# LCDCommonBoard.net
KiCad netlist of a schematic drawn in Altium Designer
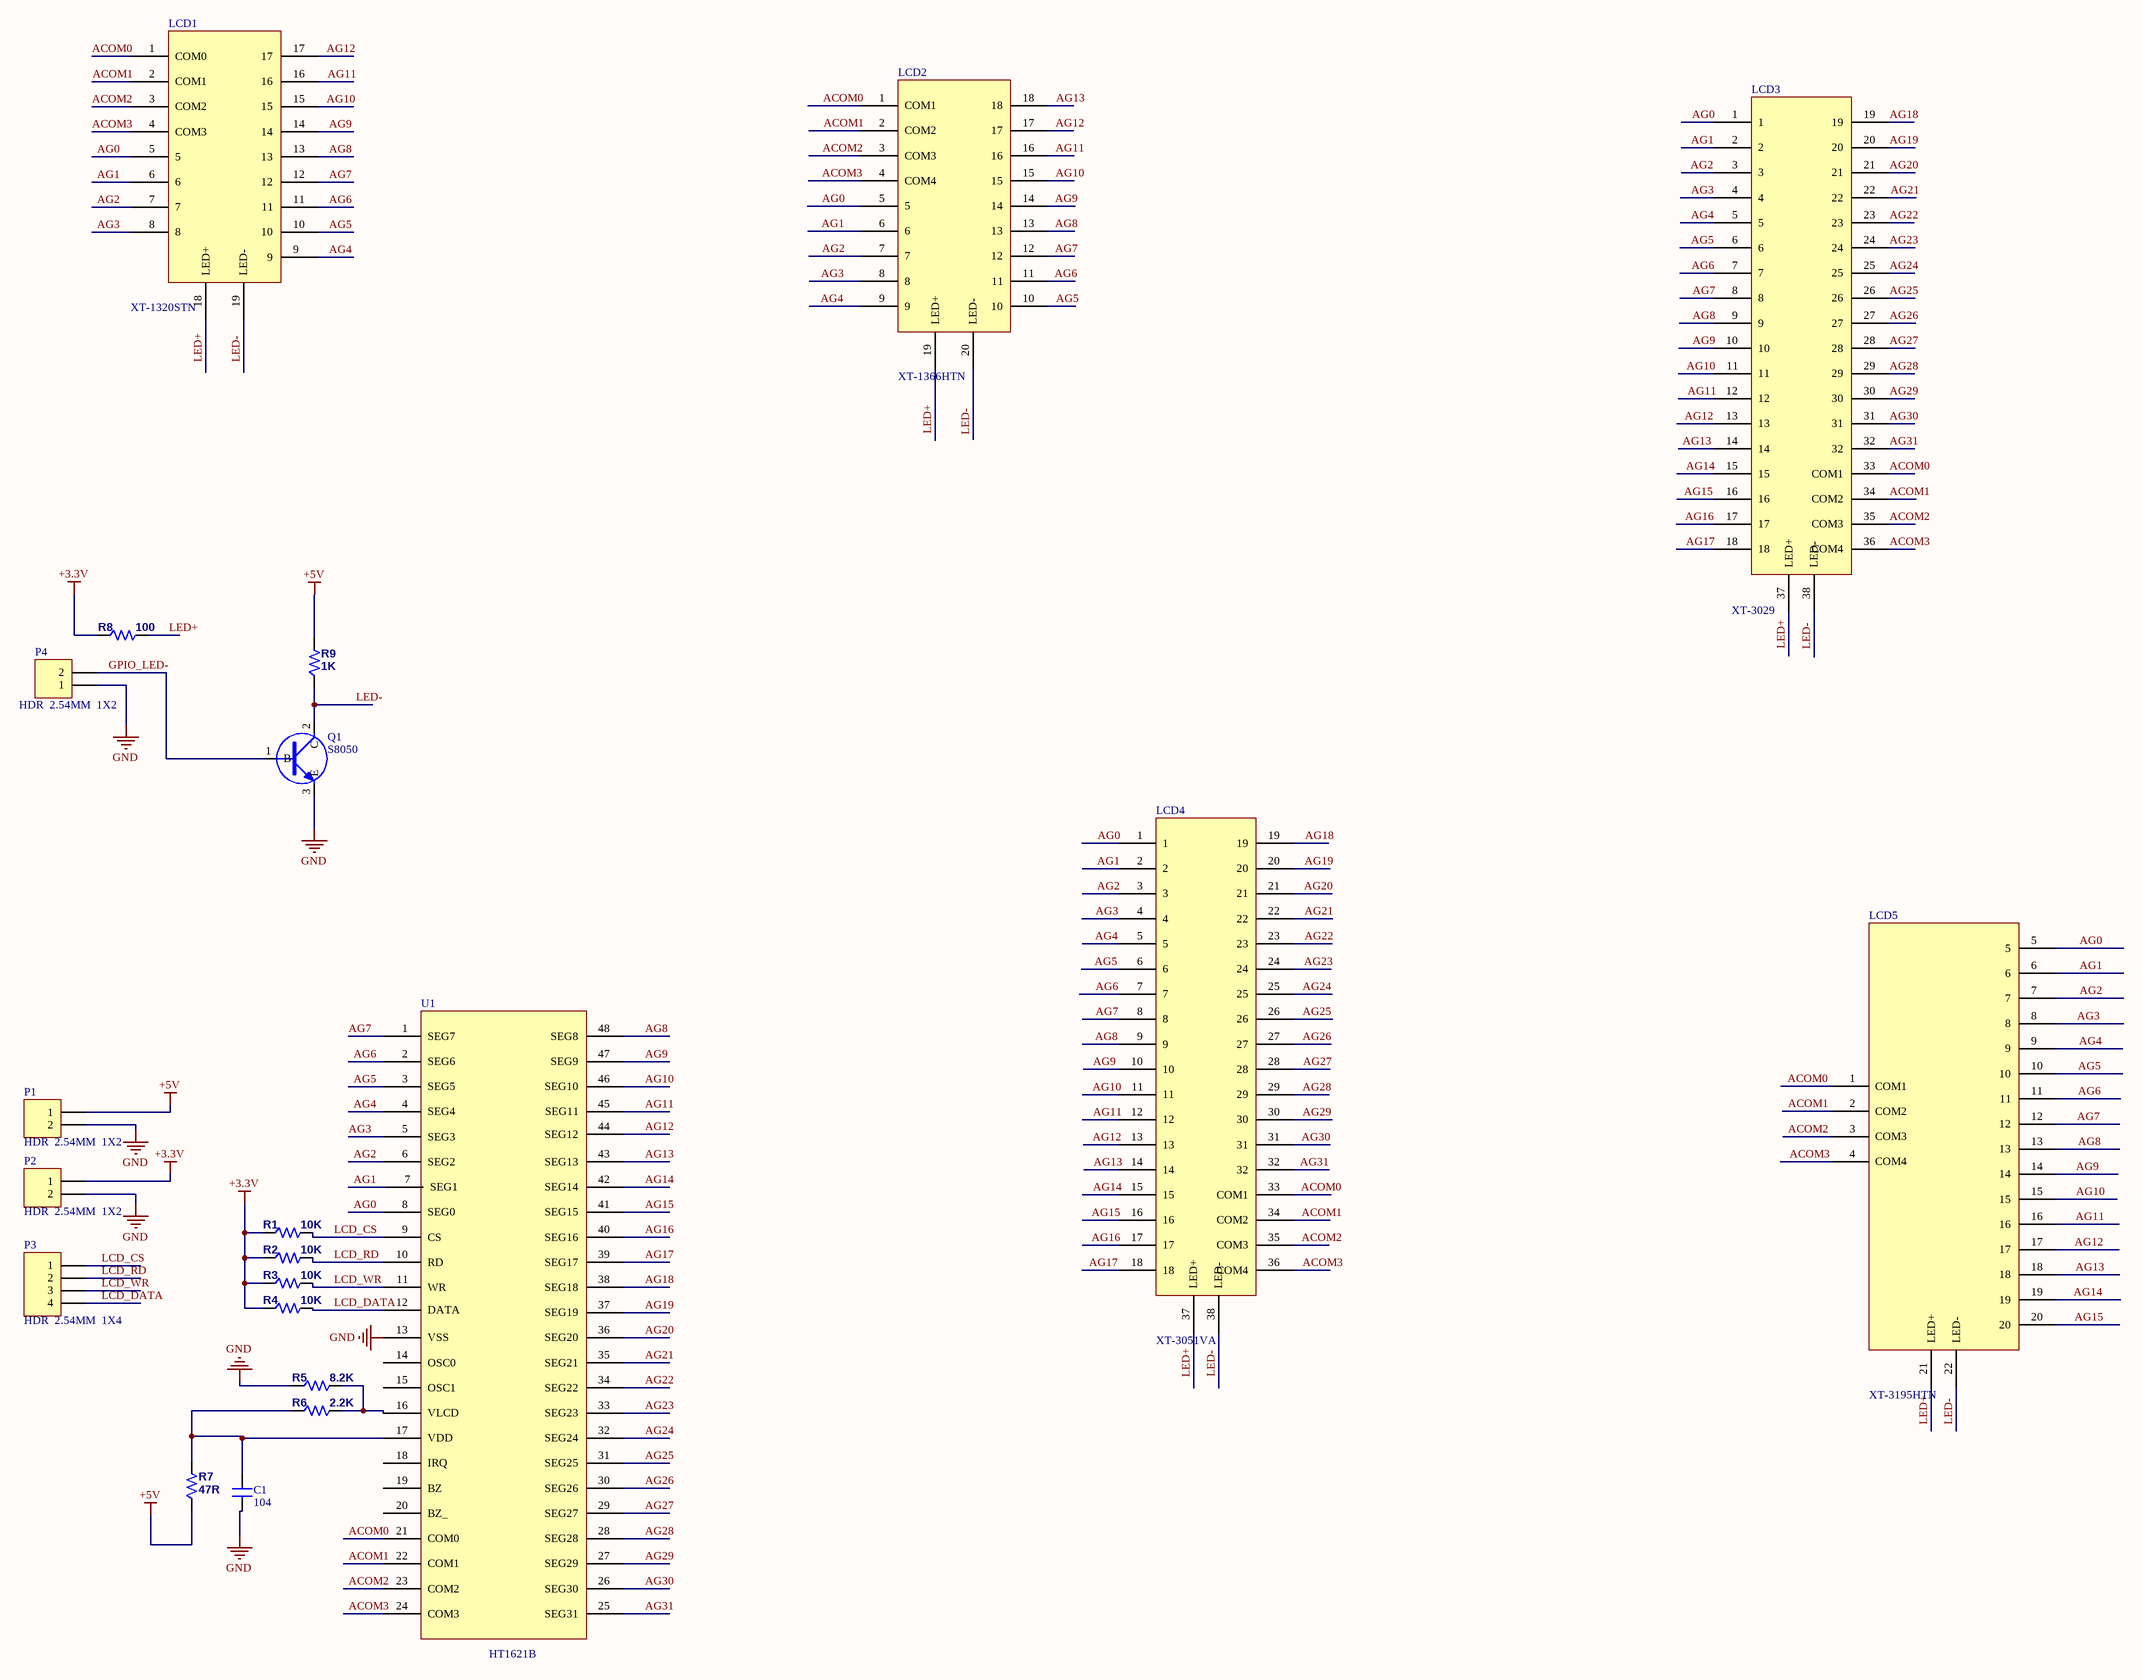
[diagram p0: LCDCommonBoard.SchDoc]

(export (version "E")
  (design (tool "Eeschema 10.0.6"))
  (components
    (comp (ref "C1")
      (value "104")
      (footprint "C0603")
      (description "查不到")
      (libsource (lib "兰格封装") (part "CAP1_60"))
    )
    (comp (ref "LCD1")
      (value "XT-1320STN")
      (footprint "LCD_8+9PIN_21X22")
      (libsource (lib "LCD") (part "XT-1320STN"))
    )
    (comp (ref "LCD2")
      (value "XT-1366HTN")
      (footprint "LCD_18PIN_20X16")
      (libsource (lib "LCD") (part "XT-1366HTN"))
    )
    (comp (ref "LCD3")
      (value "XT-3029")
      (footprint "LCD_36PIN_93X33")
      (libsource (lib "LCD") (part "XT-3029"))
    )
    (comp (ref "LCD4")
      (value "XT-3051VA")
      (footprint "LCD_36PIN_68x26.4")
      (libsource (lib "LCD") (part "XT-3051VA"))
    )
    (comp (ref "LCD5")
      (value "XT-3195HTN")
      (footprint "LCD_4+16PIN_15.5x22")
      (libsource (lib "LCD") (part "XT-3195HTN"))
    )
    (comp (ref "P1")
      (value "HDR  2.54MM  1X2")
      (footprint "HDR-1x2")
      (libsource (lib "排针排座") (part "HDR  2.54MM  1X2"))
    )
    (comp (ref "P2")
      (value "HDR  2.54MM  1X2")
      (footprint "HDR-1x2")
      (libsource (lib "排针排座") (part "HDR  2.54MM  1X2"))
    )
    (comp (ref "P3")
      (value "HDR  2.54MM  1X4")
      (footprint "HDR-1X4")
      (libsource (lib "排针排座") (part "HDR  2.54MM  1X4"))
    )
    (comp (ref "P4")
      (value "HDR  2.54MM  1X2")
      (footprint "HDR-1x2")
      (libsource (lib "") (part "HDR  2.54MM  1X2_1"))
    )
    (comp (ref "Q1") (value "S8050") (footprint "SOT 23") (libsource (lib "兰格封装") (part "NPN  东芝管2SA5200")))
    (comp (ref "R1")
      (value "10K")
      (footprint "R0603")
      (description "1206  K  5%  HS  贴片电阻")
      (libsource (lib "兰格封装") (part "RES1"))
    )
    (comp (ref "R2")
      (value "10K")
      (footprint "R0603")
      (description "1206  K  5%  HS  贴片电阻")
      (libsource (lib "兰格封装") (part "RES1"))
    )
    (comp (ref "R3")
      (value "10K")
      (footprint "R0603")
      (description "1206  K  5%  HS  贴片电阻")
      (libsource (lib "兰格封装") (part "RES1"))
    )
    (comp (ref "R4")
      (value "10K")
      (footprint "R0603")
      (description "1206  K  5%  HS  贴片电阻")
      (libsource (lib "兰格封装") (part "RES1"))
    )
    (comp (ref "R5")
      (value "8.2K")
      (footprint "R0603")
      (description "1206  K  5%  HS  贴片电阻")
      (libsource (lib "兰格封装") (part "RES1"))
    )
    (comp (ref "R6")
      (value "2.2K")
      (footprint "R0603")
      (description "1206  K  5%  HS  贴片电阻")
      (libsource (lib "兰格封装") (part "RES1"))
    )
    (comp (ref "R7")
      (value "47R")
      (footprint "R0603")
      (description "1206  K  5%  HS  贴片电阻")
      (libsource (lib "兰格封装") (part "RES1"))
    )
    (comp (ref "R8")
      (value "100")
      (footprint "R0805")
      (description "1206  K  5%  HS  贴片电阻")
      (libsource (lib "兰格封装") (part "RES1"))
    )
    (comp (ref "R9")
      (value "1K")
      (footprint "R0603")
      (description "1206  K  5%  HS  贴片电阻")
      (libsource (lib "兰格封装") (part "RES1"))
    )
    (comp (ref "U1") (value "HT1621B") (footprint "SSOP-48") (libsource (lib "集成IC") (part "HT1621B")))
  )
  (nets
    (net (code "1") (name "+3.3V") (class "Default")
      (node (ref "P2") (pin "1") (pinfunction "1_1") (pintype "passive"))
      (node (ref "R1") (pin "1") (pintype "passive"))
      (node (ref "R2") (pin "1") (pintype "passive"))
      (node (ref "R3") (pin "1") (pintype "passive"))
      (node (ref "R4") (pin "1") (pintype "passive"))
      (node (ref "R8") (pin "1") (pintype "passive"))
    )
    (net (code "2") (name "+5V") (class "Default")
      (node (ref "P1") (pin "1") (pinfunction "1_1") (pintype "passive"))
      (node (ref "R7") (pin "1") (pintype "passive"))
      (node (ref "R9") (pin "2") (pintype "passive"))
    )
    (net (code "3") (name "/ACOM0") (class "Default")
      (node (ref "LCD1") (pin "1") (pinfunction "COM0_1") (pintype "passive"))
      (node (ref "LCD2") (pin "1") (pinfunction "COM1_1") (pintype "passive"))
      (node (ref "LCD3") (pin "33") (pinfunction "COM1_33") (pintype "passive"))
      (node (ref "LCD4") (pin "33") (pinfunction "COM1_33") (pintype "passive"))
      (node (ref "LCD5") (pin "1") (pinfunction "COM1_1") (pintype "passive"))
      (node (ref "U1") (pin "21") (pinfunction "COM0_21") (pintype "passive"))
    )
    (net (code "4") (name "/ACOM1") (class "Default")
      (node (ref "LCD1") (pin "2") (pinfunction "COM1_2") (pintype "passive"))
      (node (ref "LCD2") (pin "2") (pinfunction "COM2_2") (pintype "passive"))
      (node (ref "LCD3") (pin "34") (pinfunction "COM2_34") (pintype "passive"))
      (node (ref "LCD4") (pin "34") (pinfunction "COM2_34") (pintype "passive"))
      (node (ref "LCD5") (pin "2") (pinfunction "COM2_2") (pintype "passive"))
      (node (ref "U1") (pin "22") (pinfunction "COM1_22") (pintype "passive"))
    )
    (net (code "5") (name "/ACOM2") (class "Default")
      (node (ref "LCD1") (pin "3") (pinfunction "COM2_3") (pintype "passive"))
      (node (ref "LCD2") (pin "3") (pinfunction "COM3_3") (pintype "passive"))
      (node (ref "LCD3") (pin "35") (pinfunction "COM3_35") (pintype "passive"))
      (node (ref "LCD4") (pin "35") (pinfunction "COM3_35") (pintype "passive"))
      (node (ref "LCD5") (pin "3") (pinfunction "COM3_3") (pintype "passive"))
      (node (ref "U1") (pin "23") (pinfunction "COM2_23") (pintype "passive"))
    )
    (net (code "6") (name "/ACOM3") (class "Default")
      (node (ref "LCD1") (pin "4") (pinfunction "COM3_4") (pintype "passive"))
      (node (ref "LCD2") (pin "4") (pinfunction "COM4_4") (pintype "passive"))
      (node (ref "LCD3") (pin "36") (pinfunction "COM4_36") (pintype "passive"))
      (node (ref "LCD4") (pin "36") (pinfunction "COM4_36") (pintype "passive"))
      (node (ref "LCD5") (pin "4") (pinfunction "COM4_4") (pintype "passive"))
      (node (ref "U1") (pin "24") (pinfunction "COM3_24") (pintype "passive"))
    )
    (net (code "7") (name "/AG0") (class "Default")
      (node (ref "LCD1") (pin "5") (pinfunction "5_5") (pintype "passive"))
      (node (ref "LCD2") (pin "5") (pinfunction "5_5") (pintype "passive"))
      (node (ref "LCD3") (pin "1") (pinfunction "1_1") (pintype "passive"))
      (node (ref "LCD4") (pin "1") (pinfunction "1_1") (pintype "passive"))
      (node (ref "LCD5") (pin "5") (pinfunction "5_5") (pintype "passive"))
      (node (ref "U1") (pin "8") (pinfunction "SEG0_8") (pintype "passive"))
    )
    (net (code "8") (name "/AG1") (class "Default")
      (node (ref "LCD1") (pin "6") (pinfunction "6_6") (pintype "passive"))
      (node (ref "LCD2") (pin "6") (pinfunction "6_6") (pintype "passive"))
      (node (ref "LCD3") (pin "2") (pinfunction "2_2") (pintype "passive"))
      (node (ref "LCD4") (pin "2") (pinfunction "2_2") (pintype "passive"))
      (node (ref "LCD5") (pin "6") (pinfunction "6_6") (pintype "passive"))
      (node (ref "U1") (pin "7") (pinfunction "SEG1_7") (pintype "passive"))
    )
    (net (code "9") (name "/AG2") (class "Default")
      (node (ref "LCD1") (pin "7") (pinfunction "7_7") (pintype "passive"))
      (node (ref "LCD2") (pin "7") (pinfunction "7_7") (pintype "passive"))
      (node (ref "LCD3") (pin "3") (pinfunction "3_3") (pintype "passive"))
      (node (ref "LCD4") (pin "3") (pinfunction "3_3") (pintype "passive"))
      (node (ref "LCD5") (pin "7") (pinfunction "7_7") (pintype "passive"))
      (node (ref "U1") (pin "6") (pinfunction "SEG2_6") (pintype "passive"))
    )
    (net (code "10") (name "/AG3") (class "Default")
      (node (ref "LCD1") (pin "8") (pinfunction "8_8") (pintype "passive"))
      (node (ref "LCD2") (pin "8") (pinfunction "8_8") (pintype "passive"))
      (node (ref "LCD3") (pin "4") (pinfunction "4_4") (pintype "passive"))
      (node (ref "LCD4") (pin "4") (pinfunction "4_4") (pintype "passive"))
      (node (ref "LCD5") (pin "8") (pinfunction "8_8") (pintype "passive"))
      (node (ref "U1") (pin "5") (pinfunction "SEG3_5") (pintype "passive"))
    )
    (net (code "11") (name "/AG4") (class "Default")
      (node (ref "LCD1") (pin "9") (pinfunction "9_9") (pintype "passive"))
      (node (ref "LCD2") (pin "9") (pinfunction "9_9") (pintype "passive"))
      (node (ref "LCD3") (pin "5") (pinfunction "5_5") (pintype "passive"))
      (node (ref "LCD4") (pin "5") (pinfunction "5_5") (pintype "passive"))
      (node (ref "LCD5") (pin "9") (pinfunction "9_9") (pintype "passive"))
      (node (ref "U1") (pin "4") (pinfunction "SEG4_4") (pintype "passive"))
    )
    (net (code "12") (name "/AG5") (class "Default")
      (node (ref "LCD1") (pin "10") (pinfunction "10_10") (pintype "passive"))
      (node (ref "LCD2") (pin "10") (pinfunction "10_10") (pintype "passive"))
      (node (ref "LCD3") (pin "6") (pinfunction "6_6") (pintype "passive"))
      (node (ref "LCD4") (pin "6") (pinfunction "6_6") (pintype "passive"))
      (node (ref "LCD5") (pin "10") (pinfunction "10_10") (pintype "passive"))
      (node (ref "U1") (pin "3") (pinfunction "SEG5_3") (pintype "passive"))
    )
    (net (code "13") (name "/AG6") (class "Default")
      (node (ref "LCD1") (pin "11") (pinfunction "11_11") (pintype "passive"))
      (node (ref "LCD2") (pin "11") (pinfunction "11_11") (pintype "passive"))
      (node (ref "LCD3") (pin "7") (pinfunction "7_7") (pintype "passive"))
      (node (ref "LCD4") (pin "7") (pinfunction "7_7") (pintype "passive"))
      (node (ref "LCD5") (pin "11") (pinfunction "11_11") (pintype "passive"))
      (node (ref "U1") (pin "2") (pinfunction "SEG6_2") (pintype "passive"))
    )
    (net (code "14") (name "/AG7") (class "Default")
      (node (ref "LCD1") (pin "12") (pinfunction "12_12") (pintype "passive"))
      (node (ref "LCD2") (pin "12") (pinfunction "12_12") (pintype "passive"))
      (node (ref "LCD3") (pin "8") (pinfunction "8_8") (pintype "passive"))
      (node (ref "LCD4") (pin "8") (pinfunction "8_8") (pintype "passive"))
      (node (ref "LCD5") (pin "12") (pinfunction "12_12") (pintype "passive"))
      (node (ref "U1") (pin "1") (pinfunction "SEG7_1") (pintype "passive"))
    )
    (net (code "15") (name "/AG8") (class "Default")
      (node (ref "LCD1") (pin "13") (pinfunction "13_13") (pintype "passive"))
      (node (ref "LCD2") (pin "13") (pinfunction "13_13") (pintype "passive"))
      (node (ref "LCD3") (pin "9") (pinfunction "9_9") (pintype "passive"))
      (node (ref "LCD4") (pin "9") (pinfunction "9_9") (pintype "passive"))
      (node (ref "LCD5") (pin "13") (pinfunction "13_13") (pintype "passive"))
      (node (ref "U1") (pin "48") (pinfunction "SEG8_48") (pintype "passive"))
    )
    (net (code "16") (name "/AG9") (class "Default")
      (node (ref "LCD1") (pin "14") (pinfunction "14_14") (pintype "passive"))
      (node (ref "LCD2") (pin "14") (pinfunction "14_14") (pintype "passive"))
      (node (ref "LCD3") (pin "10") (pinfunction "10_10") (pintype "passive"))
      (node (ref "LCD4") (pin "10") (pinfunction "10_10") (pintype "passive"))
      (node (ref "LCD5") (pin "14") (pinfunction "14_14") (pintype "passive"))
      (node (ref "U1") (pin "47") (pinfunction "SEG9_47") (pintype "passive"))
    )
    (net (code "17") (name "/AG10") (class "Default")
      (node (ref "LCD1") (pin "15") (pinfunction "15_15") (pintype "passive"))
      (node (ref "LCD2") (pin "15") (pinfunction "15_15") (pintype "passive"))
      (node (ref "LCD3") (pin "11") (pinfunction "11_11") (pintype "passive"))
      (node (ref "LCD4") (pin "11") (pinfunction "11_11") (pintype "passive"))
      (node (ref "LCD5") (pin "15") (pinfunction "15_15") (pintype "passive"))
      (node (ref "U1") (pin "46") (pinfunction "SEG10_46") (pintype "passive"))
    )
    (net (code "18") (name "/AG11") (class "Default")
      (node (ref "LCD1") (pin "16") (pinfunction "16_16") (pintype "passive"))
      (node (ref "LCD2") (pin "16") (pinfunction "16_16") (pintype "passive"))
      (node (ref "LCD3") (pin "12") (pinfunction "12_12") (pintype "passive"))
      (node (ref "LCD4") (pin "12") (pinfunction "12_12") (pintype "passive"))
      (node (ref "LCD5") (pin "16") (pinfunction "16_16") (pintype "passive"))
      (node (ref "U1") (pin "45") (pinfunction "SEG11_45") (pintype "passive"))
    )
    (net (code "19") (name "/AG12") (class "Default")
      (node (ref "LCD1") (pin "17") (pinfunction "17_17") (pintype "passive"))
      (node (ref "LCD2") (pin "17") (pinfunction "17_17") (pintype "passive"))
      (node (ref "LCD3") (pin "13") (pinfunction "13_13") (pintype "passive"))
      (node (ref "LCD4") (pin "13") (pinfunction "13_13") (pintype "passive"))
      (node (ref "LCD5") (pin "17") (pinfunction "17_17") (pintype "passive"))
      (node (ref "U1") (pin "44") (pinfunction "SEG12_44") (pintype "passive"))
    )
    (net (code "20") (name "/AG13") (class "Default")
      (node (ref "LCD2") (pin "18") (pinfunction "18_18") (pintype "passive"))
      (node (ref "LCD3") (pin "14") (pinfunction "14_14") (pintype "passive"))
      (node (ref "LCD4") (pin "14") (pinfunction "14_14") (pintype "passive"))
      (node (ref "LCD5") (pin "18") (pinfunction "18_18") (pintype "passive"))
      (node (ref "U1") (pin "43") (pinfunction "SEG13_43") (pintype "passive"))
    )
    (net (code "21") (name "/AG14") (class "Default")
      (node (ref "LCD3") (pin "15") (pinfunction "15_15") (pintype "passive"))
      (node (ref "LCD4") (pin "15") (pinfunction "15_15") (pintype "passive"))
      (node (ref "LCD5") (pin "19") (pinfunction "19_19") (pintype "passive"))
      (node (ref "U1") (pin "42") (pinfunction "SEG14_42") (pintype "passive"))
    )
    (net (code "22") (name "/AG15") (class "Default")
      (node (ref "LCD3") (pin "16") (pinfunction "16_16") (pintype "passive"))
      (node (ref "LCD4") (pin "16") (pinfunction "16_16") (pintype "passive"))
      (node (ref "LCD5") (pin "20") (pinfunction "20_20") (pintype "passive"))
      (node (ref "U1") (pin "41") (pinfunction "SEG15_41") (pintype "passive"))
    )
    (net (code "23") (name "/AG16") (class "Default")
      (node (ref "LCD3") (pin "17") (pinfunction "17_17") (pintype "passive"))
      (node (ref "LCD4") (pin "17") (pinfunction "17_17") (pintype "passive"))
      (node (ref "U1") (pin "40") (pinfunction "SEG16_40") (pintype "passive"))
    )
    (net (code "24") (name "/AG17") (class "Default")
      (node (ref "LCD3") (pin "18") (pinfunction "18_18") (pintype "passive"))
      (node (ref "LCD4") (pin "18") (pinfunction "18_18") (pintype "passive"))
      (node (ref "U1") (pin "39") (pinfunction "SEG17_39") (pintype "passive"))
    )
    (net (code "25") (name "/AG18") (class "Default")
      (node (ref "LCD3") (pin "19") (pinfunction "19_19") (pintype "passive"))
      (node (ref "LCD4") (pin "19") (pinfunction "19_19") (pintype "passive"))
      (node (ref "U1") (pin "38") (pinfunction "SEG18_38") (pintype "passive"))
    )
    (net (code "26") (name "/AG19") (class "Default")
      (node (ref "LCD3") (pin "20") (pinfunction "20_20") (pintype "passive"))
      (node (ref "LCD4") (pin "20") (pinfunction "20_20") (pintype "passive"))
      (node (ref "U1") (pin "37") (pinfunction "SEG19_37") (pintype "passive"))
    )
    (net (code "27") (name "/AG20") (class "Default")
      (node (ref "LCD3") (pin "21") (pinfunction "21_21") (pintype "passive"))
      (node (ref "LCD4") (pin "21") (pinfunction "21_21") (pintype "passive"))
      (node (ref "U1") (pin "36") (pinfunction "SEG20_36") (pintype "passive"))
    )
    (net (code "28") (name "/AG21") (class "Default")
      (node (ref "LCD3") (pin "22") (pinfunction "22_22") (pintype "passive"))
      (node (ref "LCD4") (pin "22") (pinfunction "22_22") (pintype "passive"))
      (node (ref "U1") (pin "35") (pinfunction "SEG21_35") (pintype "passive"))
    )
    (net (code "29") (name "/AG22") (class "Default")
      (node (ref "LCD3") (pin "23") (pinfunction "23_23") (pintype "passive"))
      (node (ref "LCD4") (pin "23") (pinfunction "23_23") (pintype "passive"))
      (node (ref "U1") (pin "34") (pinfunction "SEG22_34") (pintype "passive"))
    )
    (net (code "30") (name "/AG23") (class "Default")
      (node (ref "LCD3") (pin "24") (pinfunction "24_24") (pintype "passive"))
      (node (ref "LCD4") (pin "24") (pinfunction "24_24") (pintype "passive"))
      (node (ref "U1") (pin "33") (pinfunction "SEG23_33") (pintype "passive"))
    )
    (net (code "31") (name "/AG24") (class "Default")
      (node (ref "LCD3") (pin "25") (pinfunction "25_25") (pintype "passive"))
      (node (ref "LCD4") (pin "25") (pinfunction "25_25") (pintype "passive"))
      (node (ref "U1") (pin "32") (pinfunction "SEG24_32") (pintype "passive"))
    )
    (net (code "32") (name "/AG25") (class "Default")
      (node (ref "LCD3") (pin "26") (pinfunction "26_26") (pintype "passive"))
      (node (ref "LCD4") (pin "26") (pinfunction "26_26") (pintype "passive"))
      (node (ref "U1") (pin "31") (pinfunction "SEG25_31") (pintype "passive"))
    )
    (net (code "33") (name "/AG26") (class "Default")
      (node (ref "LCD3") (pin "27") (pinfunction "27_27") (pintype "passive"))
      (node (ref "LCD4") (pin "27") (pinfunction "27_27") (pintype "passive"))
      (node (ref "U1") (pin "30") (pinfunction "SEG26_30") (pintype "passive"))
    )
    (net (code "34") (name "/AG27") (class "Default")
      (node (ref "LCD3") (pin "28") (pinfunction "28_28") (pintype "passive"))
      (node (ref "LCD4") (pin "28") (pinfunction "28_28") (pintype "passive"))
      (node (ref "U1") (pin "29") (pinfunction "SEG27_29") (pintype "passive"))
    )
    (net (code "35") (name "/AG28") (class "Default")
      (node (ref "LCD3") (pin "29") (pinfunction "29_29") (pintype "passive"))
      (node (ref "LCD4") (pin "29") (pinfunction "29_29") (pintype "passive"))
      (node (ref "U1") (pin "28") (pinfunction "SEG28_28") (pintype "passive"))
    )
    (net (code "36") (name "/AG29") (class "Default")
      (node (ref "LCD3") (pin "30") (pinfunction "30_30") (pintype "passive"))
      (node (ref "LCD4") (pin "30") (pinfunction "30_30") (pintype "passive"))
      (node (ref "U1") (pin "27") (pinfunction "SEG29_27") (pintype "passive"))
    )
    (net (code "37") (name "/AG30") (class "Default")
      (node (ref "LCD3") (pin "31") (pinfunction "31_31") (pintype "passive"))
      (node (ref "LCD4") (pin "31") (pinfunction "31_31") (pintype "passive"))
      (node (ref "U1") (pin "26") (pinfunction "SEG30_26") (pintype "passive"))
    )
    (net (code "38") (name "/AG31") (class "Default")
      (node (ref "LCD3") (pin "32") (pinfunction "32_32") (pintype "passive"))
      (node (ref "LCD4") (pin "32") (pinfunction "32_32") (pintype "passive"))
      (node (ref "U1") (pin "25") (pinfunction "SEG31_25") (pintype "passive"))
    )
    (net (code "39") (name "/GPIO_LED-") (class "Default")
      (node (ref "P4") (pin "2") (pinfunction "2_2") (pintype "passive"))
      (node (ref "Q1") (pin "1") (pinfunction "B_1") (pintype "passive"))
    )
    (net (code "40") (name "/LCD_CS") (class "Default")
      (node (ref "P3") (pin "1") (pinfunction "1_1") (pintype "passive"))
      (node (ref "R1") (pin "2") (pintype "passive"))
      (node (ref "U1") (pin "9") (pinfunction "CS_9") (pintype "passive"))
    )
    (net (code "41") (name "/LCD_DATA") (class "Default")
      (node (ref "P3") (pin "4") (pinfunction "4_4") (pintype "passive"))
      (node (ref "R4") (pin "2") (pintype "passive"))
      (node (ref "U1") (pin "12") (pinfunction "DATA_12") (pintype "passive"))
    )
    (net (code "42") (name "/LCD_RD") (class "Default")
      (node (ref "P3") (pin "2") (pinfunction "2_2") (pintype "passive"))
      (node (ref "R2") (pin "2") (pintype "passive"))
      (node (ref "U1") (pin "10") (pinfunction "RD_10") (pintype "passive"))
    )
    (net (code "43") (name "/LCD_WR") (class "Default")
      (node (ref "P3") (pin "3") (pinfunction "3_3") (pintype "passive"))
      (node (ref "R3") (pin "2") (pintype "passive"))
      (node (ref "U1") (pin "11") (pinfunction "WR_11") (pintype "passive"))
    )
    (net (code "44") (name "/LED+") (class "Default")
      (node (ref "LCD1") (pin "18") (pinfunction "LED+_18") (pintype "passive"))
      (node (ref "LCD2") (pin "19") (pinfunction "LED+_19") (pintype "passive"))
      (node (ref "LCD3") (pin "37") (pinfunction "LED+_37") (pintype "passive"))
      (node (ref "LCD4") (pin "37") (pinfunction "LED+_37") (pintype "passive"))
      (node (ref "LCD5") (pin "21") (pinfunction "LED+_21") (pintype "passive"))
      (node (ref "R8") (pin "2") (pintype "passive"))
    )
    (net (code "45") (name "/LED-") (class "Default")
      (node (ref "LCD1") (pin "19") (pinfunction "LED-_19") (pintype "passive"))
      (node (ref "LCD2") (pin "20") (pinfunction "LED-_20") (pintype "passive"))
      (node (ref "LCD3") (pin "38") (pinfunction "LED-_38") (pintype "passive"))
      (node (ref "LCD4") (pin "38") (pinfunction "LED-_38") (pintype "passive"))
      (node (ref "LCD5") (pin "22") (pinfunction "LED-_22") (pintype "passive"))
      (node (ref "Q1") (pin "2") (pinfunction "C_2") (pintype "passive"))
      (node (ref "R9") (pin "1") (pintype "passive"))
    )
    (net (code "46") (name "GND") (class "Default")
      (node (ref "C1") (pin "2") (pinfunction "2_2") (pintype "passive"))
      (node (ref "P1") (pin "2") (pinfunction "2_2") (pintype "passive"))
      (node (ref "P2") (pin "2") (pinfunction "2_2") (pintype "passive"))
      (node (ref "P4") (pin "1") (pinfunction "1_1") (pintype "passive"))
      (node (ref "Q1") (pin "3") (pinfunction "E_3") (pintype "passive"))
      (node (ref "R5") (pin "1") (pintype "passive"))
      (node (ref "U1") (pin "13") (pinfunction "VSS_13") (pintype "passive"))
    )
    (net (code "47") (name "Net-(U1-VDD)") (class "Default")
      (node (ref "C1") (pin "1") (pinfunction "1_1") (pintype "passive"))
      (node (ref "R6") (pin "1") (pintype "passive"))
      (node (ref "R7") (pin "2") (pintype "passive"))
      (node (ref "U1") (pin "17") (pinfunction "VDD_17") (pintype "passive"))
    )
    (net (code "48") (name "Net-(U1-VLCD)") (class "Default")
      (node (ref "R5") (pin "2") (pintype "passive"))
      (node (ref "R6") (pin "2") (pintype "passive"))
      (node (ref "U1") (pin "16") (pinfunction "VLCD_16") (pintype "passive"))
    )
    (net (code "49") (name "unconnected-(U1-BZ-Pad19)") (class "Default")
      (node (ref "U1") (pin "19") (pinfunction "BZ_19") (pintype "passive"))
    )
    (net (code "50") (name "unconnected-(U1-BZ_-Pad20)") (class "Default")
      (node (ref "U1") (pin "20") (pinfunction "BZ__20") (pintype "passive"))
    )
    (net (code "51") (name "unconnected-(U1-IRQ-Pad18)") (class "Default")
      (node (ref "U1") (pin "18") (pinfunction "IRQ_18") (pintype "passive"))
    )
    (net (code "52") (name "unconnected-(U1-OSC0-Pad14)") (class "Default")
      (node (ref "U1") (pin "14") (pinfunction "OSC0_14") (pintype "passive"))
    )
    (net (code "53") (name "unconnected-(U1-OSC1-Pad15)") (class "Default")
      (node (ref "U1") (pin "15") (pinfunction "OSC1_15") (pintype "passive"))
    )
  )
)
